# Eingang_Ausgang_Signal.net
KiCad netlist of a schematic drawn in Altium Designer
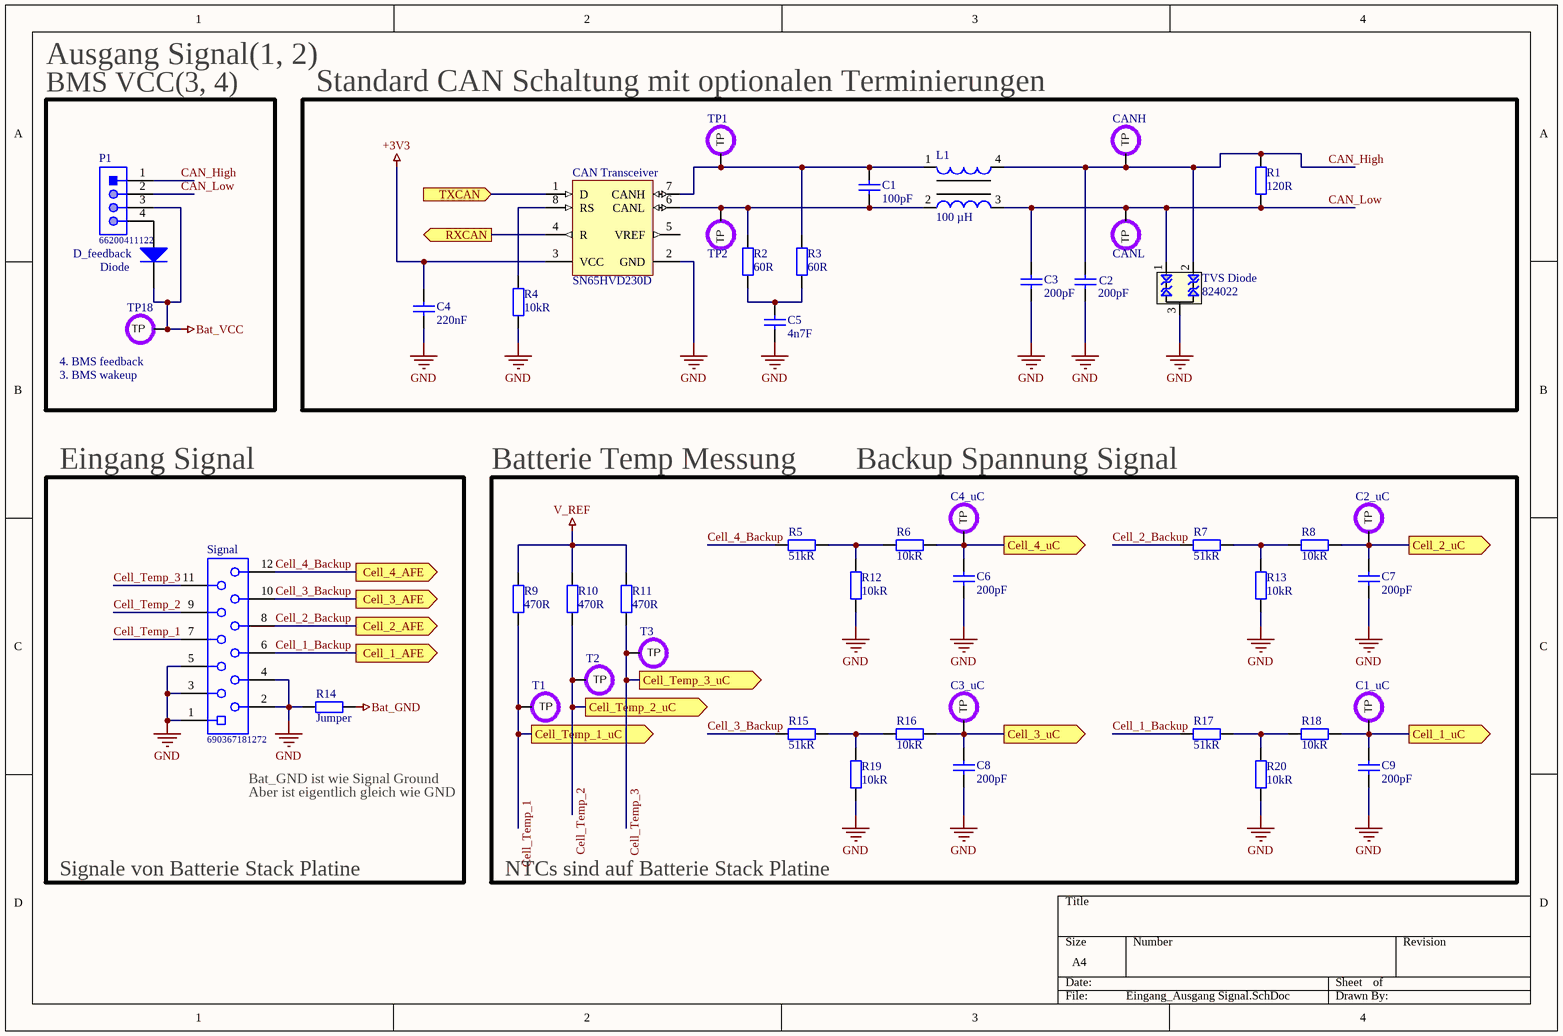
[diagram p0: Eingang_Ausgang Signal.SchDoc]

(export (version "E")
  (design (tool "Eeschema 10.0.6"))
  (components
    (comp (ref "C1")
      (value "100pF")
      (footprint "1608[0603]")
      (description "Capacitor")
      (fields (field (name "PUBLISHER") "Altium Limited"))
      (libsource (lib "Miscellaneous Devices") (part "Cap"))
    )
    (comp (ref "C1_uC")
      (value "TP_1")
      (footprint "Test point")
      (libsource (lib "Schlib1") (part "Test point"))
    )
    (comp (ref "C2")
      (value "200pF")
      (footprint "1608[0603]")
      (description "Capacitor")
      (fields (field (name "PUBLISHER") "Altium Limited"))
      (libsource (lib "Miscellaneous Devices") (part "Cap"))
    )
    (comp (ref "C2_uC")
      (value "TP_1")
      (footprint "Test point")
      (libsource (lib "Schlib1") (part "Test point"))
    )
    (comp (ref "C3")
      (value "200pF")
      (footprint "1608[0603]")
      (description "Capacitor")
      (fields (field (name "PUBLISHER") "Altium Limited"))
      (libsource (lib "Miscellaneous Devices") (part "Cap"))
    )
    (comp (ref "C3_uC")
      (value "TP_1")
      (footprint "Test point")
      (libsource (lib "Schlib1") (part "Test point"))
    )
    (comp (ref "C4")
      (value "220nF")
      (footprint "1608[0603]")
      (description "Capacitor")
      (fields (field (name "PUBLISHER") "Altium Limited"))
      (libsource (lib "Miscellaneous Devices") (part "Cap"))
    )
    (comp (ref "C4_uC")
      (value "TP_1")
      (footprint "Test point")
      (libsource (lib "Schlib1") (part "Test point"))
    )
    (comp (ref "C5")
      (value "4n7F")
      (footprint "1608[0603]")
      (description "Capacitor")
      (fields (field (name "PUBLISHER") "Altium Limited"))
      (libsource (lib "Miscellaneous Devices") (part "Cap"))
    )
    (comp (ref "C6")
      (value "200pF")
      (footprint "1608[0603]")
      (description "Capacitor")
      (fields (field (name "PUBLISHER") "Altium Limited"))
      (libsource (lib "Miscellaneous Devices") (part "Cap"))
    )
    (comp (ref "C7")
      (value "200pF")
      (footprint "1608[0603]")
      (description "Capacitor")
      (fields (field (name "PUBLISHER") "Altium Limited"))
      (libsource (lib "Miscellaneous Devices") (part "Cap"))
    )
    (comp (ref "C8")
      (value "200pF")
      (footprint "1608[0603]")
      (description "Capacitor")
      (fields (field (name "PUBLISHER") "Altium Limited"))
      (libsource (lib "Miscellaneous Devices") (part "Cap"))
    )
    (comp (ref "C9")
      (value "200pF")
      (footprint "1608[0603]")
      (description "Capacitor")
      (fields (field (name "PUBLISHER") "Altium Limited"))
      (libsource (lib "Miscellaneous Devices") (part "Cap"))
    )
    (comp (ref "CAN Transceiver")
      (value "SN65HVD230D")
      (footprint "D0008A_M")
      (description "CAN Bus Transceiver, 3.3 V, -40 to 85 degC, 8-Pin SOIC (D), Green (RoHS & no Sb/Br), Tube")
      (fields (field (name "GENERIC PART NUMBER") "SN65HVD230"))
      (libsource (lib "Altium Content Vault") (part "TI-SN65HVD230D-SOIC_D-8"))
    )
    (comp (ref "CANH")
      (value "TP_1")
      (footprint "Test point")
      (libsource (lib "Schlib1") (part "Test point"))
    )
    (comp (ref "CANL")
      (value "TP_1")
      (footprint "Test point")
      (libsource (lib "Schlib1") (part "Test point"))
    )
    (comp (ref "D_feedback")
      (value "Diode")
      (footprint "SMB")
      (description "Default Diode")
      (fields (field (name "PUBLISHER") "Altium Limited"))
      (libsource (lib "Miscellaneous Devices") (part "Diode"))
    )
    (comp (ref "L1")
      (value "100 µH")
      (footprint "WE-SLM")
      (description "SMD Common Mode Line Filter WE-SLM, L = 100 µH")
      (libsource (lib "Altium Content Vault") (part "PAS-IND-INDUCTOR-4C"))
    )
    (comp (ref "P1")
      (value "66200411122")
      (footprint "66200411122")
      (description "THT Male Header WR-MPC3, Vertical, Single Row, pitch 3 mm, 4 pins")
      (fields (field (name "MANUFACTURER") "Wurth Elektronik") (field (name "PUBLISHER") "WurthElektronik"))
      (libsource (lib "Altium Content Vault") (part "WE-CN-1P-M-R4"))
    )
    (comp (ref "R1")
      (value "120R")
      (footprint "J1-0603")
      (description "Resistor")
      (fields (field (name "PUBLISHER") "Altium Limited"))
      (libsource (lib "") (part "Res2_1"))
    )
    (comp (ref "R2")
      (value "60R")
      (footprint "J1-0603")
      (description "Resistor")
      (fields (field (name "PUBLISHER") "Altium Limited"))
      (libsource (lib "") (part "Res2_1"))
    )
    (comp (ref "R3")
      (value "60R")
      (footprint "J1-0603")
      (description "Resistor")
      (fields (field (name "PUBLISHER") "Altium Limited"))
      (libsource (lib "") (part "Res2_1"))
    )
    (comp (ref "R4")
      (value "10kR")
      (footprint "J1-0603")
      (description "Resistor")
      (fields (field (name "PUBLISHER") "Altium Limited"))
      (libsource (lib "") (part "Res2_1"))
    )
    (comp (ref "R5")
      (value "51kR")
      (footprint "J1-0603")
      (description "Resistor")
      (fields (field (name "PUBLISHER") "Altium Limited"))
      (libsource (lib "Miscellaneous Devices") (part "Res2"))
    )
    (comp (ref "R6")
      (value "10kR")
      (footprint "J1-0603")
      (description "Resistor")
      (fields (field (name "PUBLISHER") "Altium Limited"))
      (libsource (lib "Miscellaneous Devices") (part "Res2"))
    )
    (comp (ref "R7")
      (value "51kR")
      (footprint "J1-0603")
      (description "Resistor")
      (fields (field (name "PUBLISHER") "Altium Limited"))
      (libsource (lib "Miscellaneous Devices") (part "Res2"))
    )
    (comp (ref "R8")
      (value "10kR")
      (footprint "J1-0603")
      (description "Resistor")
      (fields (field (name "PUBLISHER") "Altium Limited"))
      (libsource (lib "Miscellaneous Devices") (part "Res2"))
    )
    (comp (ref "R9")
      (value "470R")
      (footprint "J1-0603")
      (description "Resistor")
      (fields (field (name "PUBLISHER") "Altium Limited"))
      (libsource (lib "") (part "Res2_1"))
    )
    (comp (ref "R10")
      (value "470R")
      (footprint "J1-0603")
      (description "Resistor")
      (fields (field (name "PUBLISHER") "Altium Limited"))
      (libsource (lib "") (part "Res2_1"))
    )
    (comp (ref "R11")
      (value "470R")
      (footprint "J1-0603")
      (description "Resistor")
      (fields (field (name "PUBLISHER") "Altium Limited"))
      (libsource (lib "") (part "Res2_1"))
    )
    (comp (ref "R12")
      (value "10kR")
      (footprint "J1-0603")
      (description "Resistor")
      (fields (field (name "PUBLISHER") "Altium Limited"))
      (libsource (lib "") (part "Res2_1"))
    )
    (comp (ref "R13")
      (value "10kR")
      (footprint "J1-0603")
      (description "Resistor")
      (fields (field (name "PUBLISHER") "Altium Limited"))
      (libsource (lib "") (part "Res2_1"))
    )
    (comp (ref "R14")
      (value "Jumper")
      (footprint "J1-0603")
      (description "Resistor")
      (fields (field (name "PUBLISHER") "Altium Limited"))
      (libsource (lib "Miscellaneous Devices") (part "Res2"))
    )
    (comp (ref "R15")
      (value "51kR")
      (footprint "J1-0603")
      (description "Resistor")
      (fields (field (name "PUBLISHER") "Altium Limited"))
      (libsource (lib "Miscellaneous Devices") (part "Res2"))
    )
    (comp (ref "R16")
      (value "10kR")
      (footprint "J1-0603")
      (description "Resistor")
      (fields (field (name "PUBLISHER") "Altium Limited"))
      (libsource (lib "Miscellaneous Devices") (part "Res2"))
    )
    (comp (ref "R17")
      (value "51kR")
      (footprint "J1-0603")
      (description "Resistor")
      (fields (field (name "PUBLISHER") "Altium Limited"))
      (libsource (lib "Miscellaneous Devices") (part "Res2"))
    )
    (comp (ref "R18")
      (value "10kR")
      (footprint "J1-0603")
      (description "Resistor")
      (fields (field (name "PUBLISHER") "Altium Limited"))
      (libsource (lib "Miscellaneous Devices") (part "Res2"))
    )
    (comp (ref "R19")
      (value "10kR")
      (footprint "J1-0603")
      (description "Resistor")
      (fields (field (name "PUBLISHER") "Altium Limited"))
      (libsource (lib "") (part "Res2_1"))
    )
    (comp (ref "R20")
      (value "10kR")
      (footprint "J1-0603")
      (description "Resistor")
      (fields (field (name "PUBLISHER") "Altium Limited"))
      (libsource (lib "") (part "Res2_1"))
    )
    (comp (ref "Signal")
      (value "690367181272")
      (footprint "690367181272")
      (description "Female THT Straight Connector without Latch and without Polarization WR-MM, 12 pins")
      (fields (field (name "MANUFACTURER") "Wurth Elektronik") (field (name "PUBLISHER") "WurthElektronik"))
      (libsource (lib "Altium Content Vault") (part "WE-CN-2S-F-R12"))
    )
    (comp (ref "T1") (value "TP_1") (footprint "Test point") (libsource (lib "Schlib1") (part "Test point")))
    (comp (ref "T2") (value "TP_1") (footprint "Test point") (libsource (lib "Schlib1") (part "Test point")))
    (comp (ref "T3") (value "TP_1") (footprint "Test point") (libsource (lib "Schlib1") (part "Test point")))
    (comp (ref "TP1") (value "TP_1") (footprint "Test point") (libsource (lib "Schlib1") (part "Test point")))
    (comp (ref "TP2") (value "TP_1") (footprint "Test point") (libsource (lib "Schlib1") (part "Test point")))
    (comp (ref "TP18")
      (value "TP_1")
      (footprint "Test point")
      (libsource (lib "Schlib1") (part "Test point"))
    )
    (comp (ref "TVS Diode")
      (value "824022")
      (footprint "SOT23_3L")
      (description "TVS Diode WE-TVS-Standard, VRWM=5.0V")
      (fields (field (name "MANUFACTURER") "Wuerth Elektronik"))
      (libsource (lib "Altium Content Vault") (part "WE-824022-3"))
    )
  )
  (nets
    (net (code "1") (name "+3V3") (class "Default")
      (node (ref "C4") (pin "2") (pinfunction "2_2") (pintype "passive"))
      (node (ref "CAN Transceiver") (pin "3") (pinfunction "VCC_3") (pintype "power_in"))
    )
    (net (code "2") (name "/CAN_High") (class "Default")
      (node (ref "C2") (pin "2") (pinfunction "2_2") (pintype "passive"))
      (node (ref "CANH") (pin "1") (pinfunction "TP_1") (pintype "passive"))
      (node (ref "L1") (pin "4") (pinfunction "4_4") (pintype "passive"))
      (node (ref "P1") (pin "1") (pinfunction "1_1") (pintype "passive"))
      (node (ref "R1") (pin "2") (pinfunction "2_2") (pintype "passive"))
      (node (ref "TVS Diode") (pin "2") (pinfunction "I/O_2") (pintype "passive"))
    )
    (net (code "3") (name "/CAN_Low") (class "Default")
      (node (ref "C3") (pin "2") (pinfunction "2_2") (pintype "passive"))
      (node (ref "CANL") (pin "1") (pinfunction "TP_1") (pintype "passive"))
      (node (ref "L1") (pin "3") (pinfunction "3_3") (pintype "passive"))
      (node (ref "P1") (pin "2") (pinfunction "2_2") (pintype "passive"))
      (node (ref "R1") (pin "1") (pinfunction "1_1") (pintype "passive"))
      (node (ref "TVS Diode") (pin "1") (pinfunction "I/O_1") (pintype "passive"))
    )
    (net (code "4") (name "/Cell_1_Backup") (class "Default")
      (node (ref "R17") (pin "2") (pinfunction "2_2") (pintype "passive"))
      (node (ref "Signal") (pin "6") (pinfunction "6_6") (pintype "passive"))
    )
    (net (code "5") (name "/Cell_1_uC") (class "Default")
      (node (ref "C1_uC") (pin "1") (pinfunction "TP_1") (pintype "passive"))
      (node (ref "C9") (pin "2") (pinfunction "2_2") (pintype "passive"))
      (node (ref "R18") (pin "1") (pinfunction "1_1") (pintype "passive"))
    )
    (net (code "6") (name "/Cell_2_Backup") (class "Default")
      (node (ref "R7") (pin "2") (pinfunction "2_2") (pintype "passive"))
      (node (ref "Signal") (pin "8") (pinfunction "8_8") (pintype "passive"))
    )
    (net (code "7") (name "/Cell_2_uC") (class "Default")
      (node (ref "C2_uC") (pin "1") (pinfunction "TP_1") (pintype "passive"))
      (node (ref "C7") (pin "2") (pinfunction "2_2") (pintype "passive"))
      (node (ref "R8") (pin "1") (pinfunction "1_1") (pintype "passive"))
    )
    (net (code "8") (name "/Cell_3_Backup") (class "Default")
      (node (ref "R15") (pin "2") (pinfunction "2_2") (pintype "passive"))
      (node (ref "Signal") (pin "10") (pinfunction "10_10") (pintype "passive"))
    )
    (net (code "9") (name "/Cell_3_uC") (class "Default")
      (node (ref "C3_uC") (pin "1") (pinfunction "TP_1") (pintype "passive"))
      (node (ref "C8") (pin "2") (pinfunction "2_2") (pintype "passive"))
      (node (ref "R16") (pin "1") (pinfunction "1_1") (pintype "passive"))
    )
    (net (code "10") (name "/Cell_4_Backup") (class "Default")
      (node (ref "R5") (pin "2") (pinfunction "2_2") (pintype "passive"))
      (node (ref "Signal") (pin "12") (pinfunction "12_12") (pintype "passive"))
    )
    (net (code "11") (name "/Cell_4_uC") (class "Default")
      (node (ref "C4_uC") (pin "1") (pinfunction "TP_1") (pintype "passive"))
      (node (ref "C6") (pin "2") (pinfunction "2_2") (pintype "passive"))
      (node (ref "R6") (pin "1") (pinfunction "1_1") (pintype "passive"))
    )
    (net (code "12") (name "/Cell_Temp_1") (class "Default")
      (node (ref "R9") (pin "1") (pinfunction "1_1") (pintype "passive"))
      (node (ref "Signal") (pin "7") (pinfunction "7_7") (pintype "passive"))
      (node (ref "T1") (pin "1") (pinfunction "TP_1") (pintype "passive"))
    )
    (net (code "13") (name "/Cell_Temp_2") (class "Default")
      (node (ref "R10") (pin "1") (pinfunction "1_1") (pintype "passive"))
      (node (ref "Signal") (pin "9") (pinfunction "9_9") (pintype "passive"))
      (node (ref "T2") (pin "1") (pinfunction "TP_1") (pintype "passive"))
    )
    (net (code "14") (name "/Cell_Temp_3") (class "Default")
      (node (ref "R11") (pin "1") (pinfunction "1_1") (pintype "passive"))
      (node (ref "Signal") (pin "11") (pinfunction "11_11") (pintype "passive"))
      (node (ref "T3") (pin "1") (pinfunction "TP_1") (pintype "passive"))
    )
    (net (code "15") (name "/RXCAN") (class "Default")
      (node (ref "CAN Transceiver") (pin "4") (pinfunction "R_4") (pintype "output"))
    )
    (net (code "16") (name "/TXCAN") (class "Default")
      (node (ref "CAN Transceiver") (pin "1") (pinfunction "D_1") (pintype "input"))
    )
    (net (code "17") (name "Bat_GND") (class "Default")
      (node (ref "R14") (pin "1") (pinfunction "1_1") (pintype "passive"))
    )
    (net (code "18") (name "Bat_VCC") (class "Default")
      (node (ref "D_feedback") (pin "2") (pinfunction "K_2") (pintype "passive"))
      (node (ref "P1") (pin "3") (pinfunction "3_3") (pintype "passive"))
      (node (ref "TP18") (pin "1") (pinfunction "TP_1") (pintype "passive"))
    )
    (net (code "19") (name "GND") (class "Default")
      (node (ref "C2") (pin "1") (pinfunction "1_1") (pintype "passive"))
      (node (ref "C3") (pin "1") (pinfunction "1_1") (pintype "passive"))
      (node (ref "C4") (pin "1") (pinfunction "1_1") (pintype "passive"))
      (node (ref "C5") (pin "1") (pinfunction "1_1") (pintype "passive"))
      (node (ref "C6") (pin "1") (pinfunction "1_1") (pintype "passive"))
      (node (ref "C7") (pin "1") (pinfunction "1_1") (pintype "passive"))
      (node (ref "C8") (pin "1") (pinfunction "1_1") (pintype "passive"))
      (node (ref "C9") (pin "1") (pinfunction "1_1") (pintype "passive"))
      (node (ref "CAN Transceiver") (pin "2") (pinfunction "GND_2") (pintype "power_in"))
      (node (ref "R12") (pin "1") (pinfunction "1_1") (pintype "passive"))
      (node (ref "R13") (pin "1") (pinfunction "1_1") (pintype "passive"))
      (node (ref "R14") (pin "2") (pinfunction "2_2") (pintype "passive"))
      (node (ref "R19") (pin "1") (pinfunction "1_1") (pintype "passive"))
      (node (ref "R20") (pin "1") (pinfunction "1_1") (pintype "passive"))
      (node (ref "R4") (pin "1") (pinfunction "1_1") (pintype "passive"))
      (node (ref "Signal") (pin "1") (pinfunction "1_1") (pintype "passive"))
      (node (ref "Signal") (pin "2") (pinfunction "2_2") (pintype "passive"))
      (node (ref "Signal") (pin "3") (pinfunction "3_3") (pintype "passive"))
      (node (ref "Signal") (pin "4") (pinfunction "4_4") (pintype "passive"))
      (node (ref "Signal") (pin "5") (pinfunction "5_5") (pintype "passive"))
      (node (ref "TVS Diode") (pin "3") (pinfunction "GND_3") (pintype "passive"))
    )
    (net (code "20") (name "Net-(C5-Pad2)") (class "Default")
      (node (ref "C5") (pin "2") (pinfunction "2_2") (pintype "passive"))
      (node (ref "R2") (pin "1") (pinfunction "1_1") (pintype "passive"))
      (node (ref "R3") (pin "1") (pinfunction "1_1") (pintype "passive"))
    )
    (net (code "21") (name "Net-(CAN Transceiver-CANH)") (class "Default")
      (node (ref "C1") (pin "2") (pinfunction "2_2") (pintype "passive"))
      (node (ref "CAN Transceiver") (pin "7") (pinfunction "CANH_7") (pintype "bidirectional"))
      (node (ref "L1") (pin "1") (pinfunction "1_1") (pintype "passive"))
      (node (ref "R3") (pin "2") (pinfunction "2_2") (pintype "passive"))
      (node (ref "TP1") (pin "1") (pinfunction "TP_1") (pintype "passive"))
    )
    (net (code "22") (name "Net-(CAN Transceiver-CANL)") (class "Default")
      (node (ref "C1") (pin "1") (pinfunction "1_1") (pintype "passive"))
      (node (ref "CAN Transceiver") (pin "6") (pinfunction "CANL_6") (pintype "bidirectional"))
      (node (ref "L1") (pin "2") (pinfunction "2_2") (pintype "passive"))
      (node (ref "R2") (pin "2") (pinfunction "2_2") (pintype "passive"))
      (node (ref "TP2") (pin "1") (pinfunction "TP_1") (pintype "passive"))
    )
    (net (code "23") (name "Net-(CAN Transceiver-RS)") (class "Default")
      (node (ref "CAN Transceiver") (pin "8") (pinfunction "RS_8") (pintype "input"))
      (node (ref "R4") (pin "2") (pinfunction "2_2") (pintype "passive"))
    )
    (net (code "24") (name "Net-(D_feedback-A)") (class "Default")
      (node (ref "D_feedback") (pin "1") (pinfunction "A_1") (pintype "passive"))
      (node (ref "P1") (pin "4") (pinfunction "4_4") (pintype "passive"))
    )
    (net (code "25") (name "Net-(R12-Pad2)") (class "Default")
      (node (ref "R12") (pin "2") (pinfunction "2_2") (pintype "passive"))
      (node (ref "R5") (pin "1") (pinfunction "1_1") (pintype "passive"))
      (node (ref "R6") (pin "2") (pinfunction "2_2") (pintype "passive"))
    )
    (net (code "26") (name "Net-(R13-Pad2)") (class "Default")
      (node (ref "R13") (pin "2") (pinfunction "2_2") (pintype "passive"))
      (node (ref "R7") (pin "1") (pinfunction "1_1") (pintype "passive"))
      (node (ref "R8") (pin "2") (pinfunction "2_2") (pintype "passive"))
    )
    (net (code "27") (name "Net-(R15-Pad1)") (class "Default")
      (node (ref "R15") (pin "1") (pinfunction "1_1") (pintype "passive"))
      (node (ref "R16") (pin "2") (pinfunction "2_2") (pintype "passive"))
      (node (ref "R19") (pin "2") (pinfunction "2_2") (pintype "passive"))
    )
    (net (code "28") (name "Net-(R17-Pad1)") (class "Default")
      (node (ref "R17") (pin "1") (pinfunction "1_1") (pintype "passive"))
      (node (ref "R18") (pin "2") (pinfunction "2_2") (pintype "passive"))
      (node (ref "R20") (pin "2") (pinfunction "2_2") (pintype "passive"))
    )
    (net (code "29") (name "V_REF") (class "Default")
      (node (ref "R10") (pin "2") (pinfunction "2_2") (pintype "passive"))
      (node (ref "R11") (pin "2") (pinfunction "2_2") (pintype "passive"))
      (node (ref "R9") (pin "2") (pinfunction "2_2") (pintype "passive"))
    )
    (net (code "30") (name "unconnected-(CAN Transceiver-VREF-Pad5)") (class "Default")
      (node (ref "CAN Transceiver") (pin "5") (pinfunction "VREF_5") (pintype "output"))
    )
  )
)
